# Fisierul_cu_schematicul.net
KiCad netlist of a schematic drawn in EAGLE
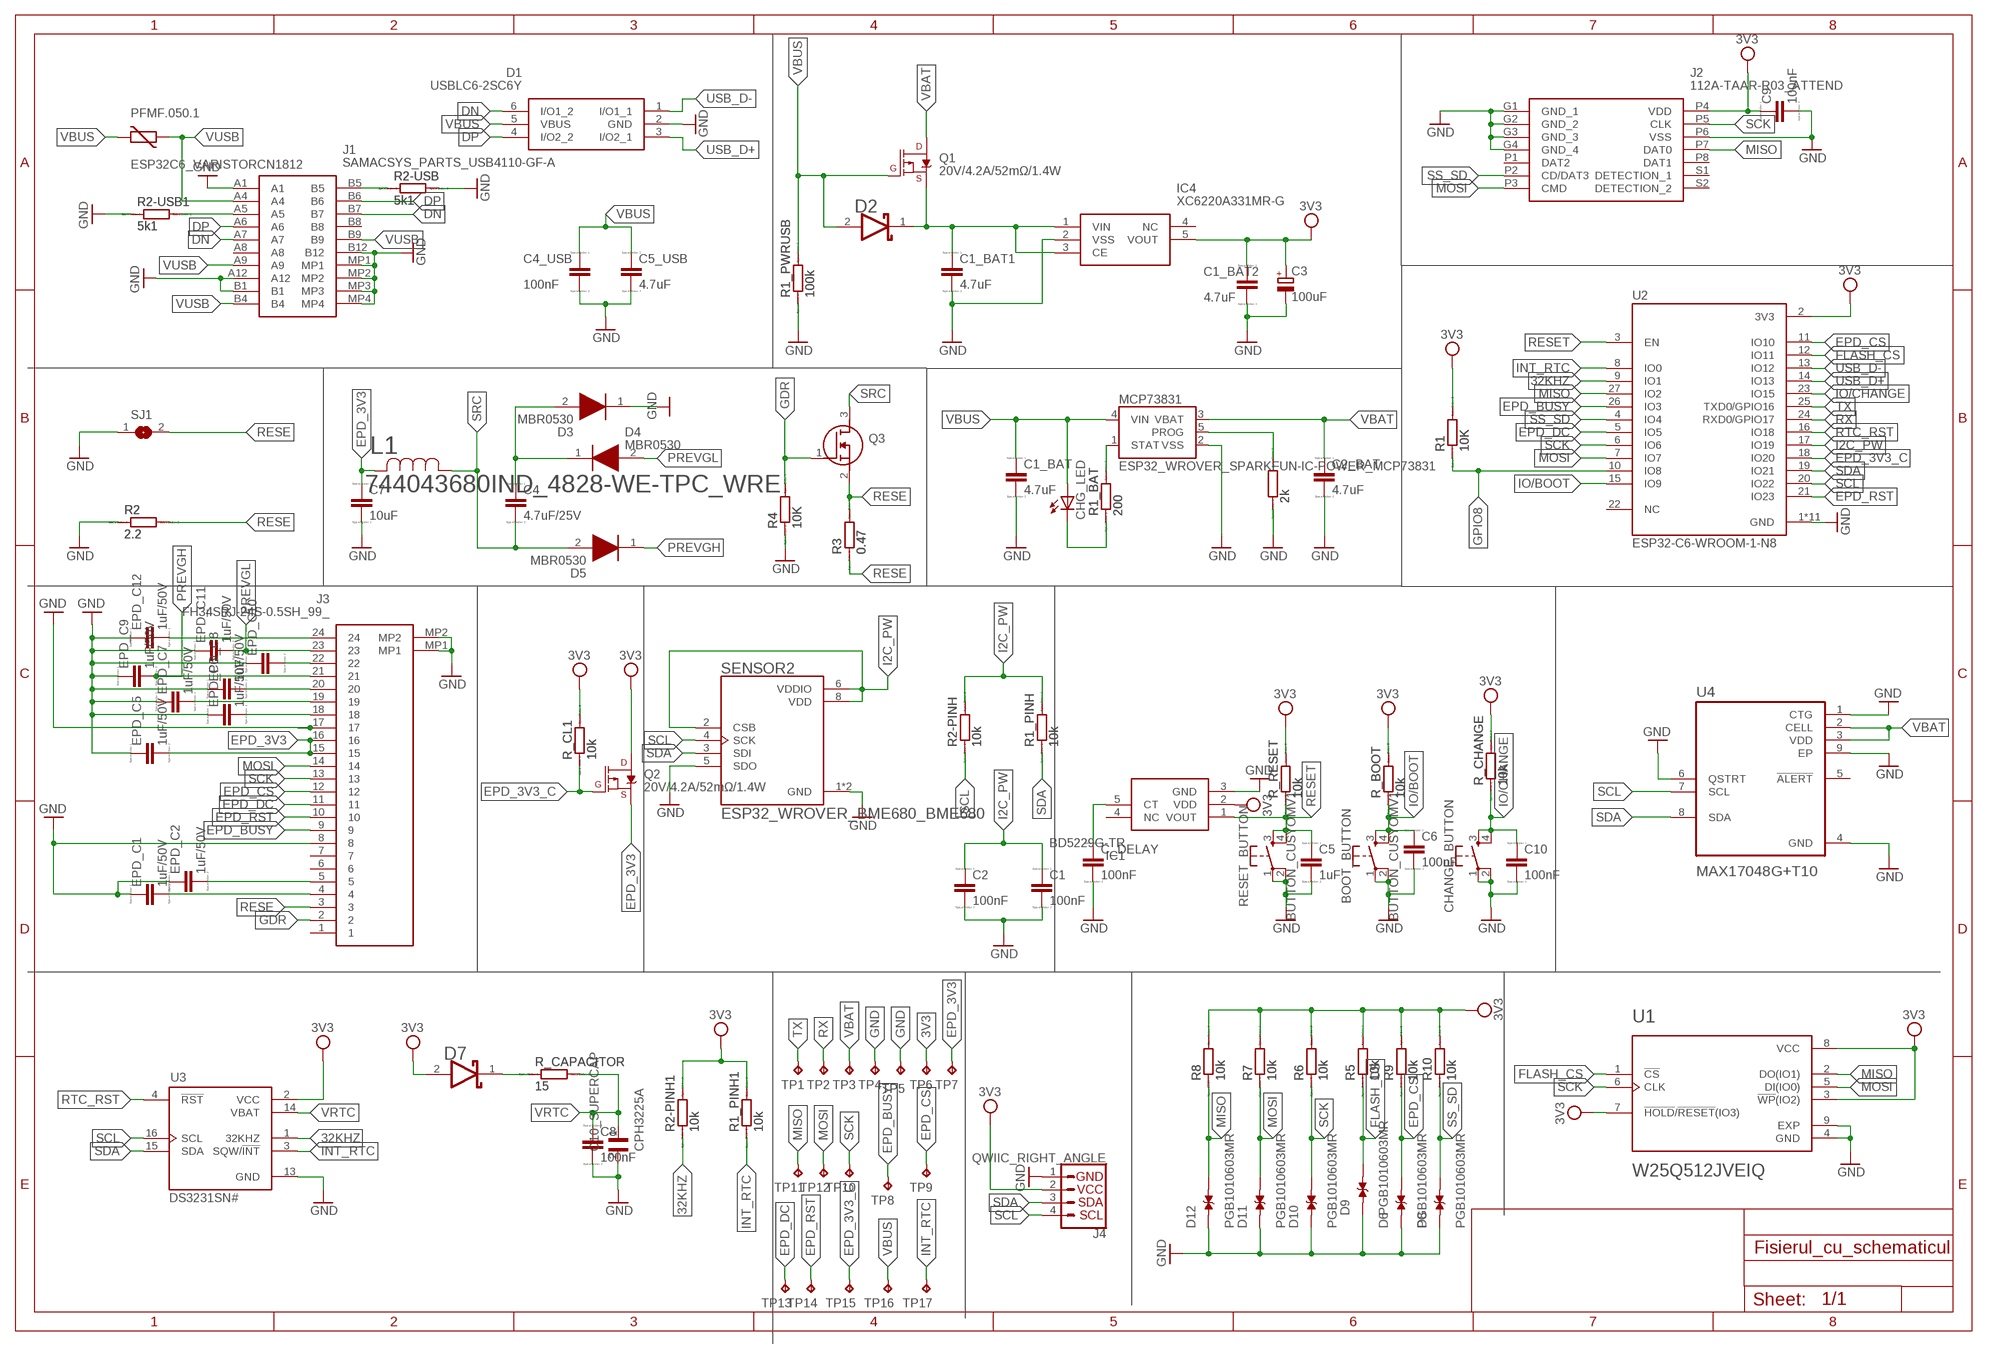
[diagram p0: schematic, sheet 1]

(export (version "E")
  (design (tool "Eeschema 10.0.6"))
  (components
    (comp (ref "BOOT_BUTTON")
      (value "BUTTON_CUSYOMV1")
      (footprint "eagle-import:MYBUTTON")
      (libsource (lib "eagle-import") (part "BUTTON_CUSYOMV1"))
    )
    (comp (ref "C1")
      (value "100nF")
      (footprint "eagle-import:EAGLE-LTSPICE_C0402")
      (libsource (lib "eagle-import") (part "EAGLE-LTSPICE_CC0402"))
    )
    (comp (ref "C1_BAT")
      (value "4.7uF")
      (footprint "eagle-import:ESP32_WROVER_EAGLE-LTSPICE_C0402")
      (libsource (lib "eagle-import") (part "ESP32_WROVER_EAGLE-LTSPICE_CC0402"))
    )
    (comp (ref "C1_BAT1")
      (value "4.7uF")
      (footprint "eagle-import:EAGLE-LTSPICE_C0402")
      (libsource (lib "eagle-import") (part "EAGLE-LTSPICE_CC0402"))
    )
    (comp (ref "C1_BAT2")
      (value "4.7uF")
      (footprint "eagle-import:EAGLE-LTSPICE_C0402")
      (libsource (lib "eagle-import") (part "EAGLE-LTSPICE_CC0402"))
    )
    (comp (ref "C2")
      (value "100nF")
      (footprint "eagle-import:EAGLE-LTSPICE_C0402")
      (libsource (lib "eagle-import") (part "EAGLE-LTSPICE_CC0402"))
    )
    (comp (ref "C2_BAT")
      (value "4.7uF")
      (footprint "eagle-import:EAGLE-LTSPICE_C0402")
      (libsource (lib "eagle-import") (part "EAGLE-LTSPICE_CC0402"))
    )
    (comp (ref "C3")
      (value "100uF")
      (footprint "eagle-import:RCL_CT3528")
      (libsource (lib "eagle-import") (part "RCL_CPOL-EUCT3528"))
    )
    (comp (ref "C4")
      (value "4.7uF/25V")
      (footprint "eagle-import:EAGLE-LTSPICE_C0402")
      (libsource (lib "eagle-import") (part "EAGLE-LTSPICE_CC0402"))
    )
    (comp (ref "C4_USB")
      (value "100nF")
      (footprint "eagle-import:ESP32_WROVER_EAGLE-LTSPICE_C0402")
      (libsource (lib "eagle-import") (part "ESP32_WROVER_EAGLE-LTSPICE_CC0402"))
    )
    (comp (ref "C5")
      (value "1uF")
      (footprint "eagle-import:EAGLE-LTSPICE_C0402")
      (libsource (lib "eagle-import") (part "EAGLE-LTSPICE_CC0402"))
    )
    (comp (ref "C5_USB")
      (value "4.7uF")
      (footprint "eagle-import:ESP32_WROVER_EAGLE-LTSPICE_C0402")
      (libsource (lib "eagle-import") (part "ESP32_WROVER_EAGLE-LTSPICE_CC0402"))
    )
    (comp (ref "C6")
      (value "100nF")
      (footprint "eagle-import:EAGLE-LTSPICE_C0402")
      (libsource (lib "eagle-import") (part "EAGLE-LTSPICE_CC0402"))
    )
    (comp (ref "C7")
      (value "10uF")
      (footprint "eagle-import:EAGLE-LTSPICE_C0402")
      (libsource (lib "eagle-import") (part "EAGLE-LTSPICE_CC0402"))
    )
    (comp (ref "C8")
      (value "100nF")
      (footprint "eagle-import:EAGLE-LTSPICE_C0402")
      (libsource (lib "eagle-import") (part "EAGLE-LTSPICE_CC0402"))
    )
    (comp (ref "C9")
      (value "100nF")
      (footprint "eagle-import:ESP32_WROVER_EAGLE-LTSPICE_C0402")
      (libsource (lib "eagle-import") (part "ESP32_WROVER_EAGLE-LTSPICE_CC0402"))
    )
    (comp (ref "C10")
      (value "100nF")
      (footprint "eagle-import:EAGLE-LTSPICE_C0402")
      (libsource (lib "eagle-import") (part "EAGLE-LTSPICE_CC0402"))
    )
    (comp (ref "C10_SUPERCAP")
      (value "CPH3225A")
      (footprint "eagle-import:CAPCP3225X100N")
      (fields (field (name "MF") "Seiko Instruments"))
      (libsource (lib "eagle-import") (part "CPH3225A"))
    )
    (comp (ref "CHANGE_BUTTON")
      (value "BUTTON_CUSYOMV1")
      (footprint "eagle-import:MYBUTTON")
      (libsource (lib "eagle-import") (part "BUTTON_CUSYOMV1"))
    )
    (comp (ref "CHG_LED")
      (value "ADAFRUIT_LEDCHIP-LED0603")
      (footprint "eagle-import:ADAFRUIT_CHIP-LED0603")
      (libsource (lib "eagle-import") (part "ADAFRUIT_LEDCHIP-LED0603"))
    )
    (comp (ref "C_DELAY")
      (value "100nF")
      (footprint "eagle-import:EAGLE-LTSPICE_C0402")
      (libsource (lib "eagle-import") (part "EAGLE-LTSPICE_CC0402"))
    )
    (comp (ref "D1")
      (value "USBLC6-2SC6Y")
      (footprint "eagle-import:SOT95P280X145-6N")
      (fields (field (name "MF") "STMicroelectronics"))
      (libsource (lib "eagle-import") (part "USBLC6-2SC6Y"))
    )
    (comp (ref "D2")
      (value "ESP32_WROVER_AVX---SD0805S020S1R0_AVX_SD0805S020S1R0_0_0AVX_SD0805S020S1R0_0_0")
      (footprint "eagle-import:ESP32_WROVER_AVX---SD0805S020S1R0_AVX_SD0805S020S1R0_0")
      (fields
        (field (name "DIGIKEY_PART_NUMBER") "478-7800-1-ND")
        (field (name "MF") "AVX")
        (field (name "MOUSER_PART_NUMBER") "581-SD0805S020S1R0")
      )
      (libsource (lib "eagle-import") (part "ESP32_WROVER_AVX---SD0805S020S1R0_AVX_SD0805S020S1R0_0_0AVX_SD0805S020S1R0_0_0"))
    )
    (comp (ref "D3")
      (value "MBR0530")
      (footprint "eagle-import:SOD3716X135N")
      (fields (field (name "MF") "ON Semiconductor"))
      (libsource (lib "eagle-import") (part "MBR0530"))
    )
    (comp (ref "D4")
      (value "MBR0530")
      (footprint "eagle-import:SOD3716X135N")
      (fields (field (name "MF") "ON Semiconductor"))
      (libsource (lib "eagle-import") (part "MBR0530"))
    )
    (comp (ref "D5")
      (value "MBR0530")
      (footprint "eagle-import:SOD3716X135N")
      (fields (field (name "MF") "ON Semiconductor"))
      (libsource (lib "eagle-import") (part "MBR0530"))
    )
    (comp (ref "D6")
      (value "PGB1010603MR")
      (footprint "eagle-import:DIOC1608X36N")
      (fields (field (name "MF") "Littelfuse Inc."))
      (libsource (lib "eagle-import") (part "PGB1010603MR"))
    )
    (comp (ref "D7")
      (value "ESP32_WROVER_AVX---SD0805S020S1R0_AVX_SD0805S020S1R0_0_0AVX_SD0805S020S1R0_0_0")
      (footprint "eagle-import:ESP32_WROVER_AVX---SD0805S020S1R0_AVX_SD0805S020S1R0_0")
      (fields
        (field (name "DIGIKEY_PART_NUMBER") "478-7800-1-ND")
        (field (name "MF") "AVX")
        (field (name "MOUSER_PART_NUMBER") "581-SD0805S020S1R0")
      )
      (libsource (lib "eagle-import") (part "ESP32_WROVER_AVX---SD0805S020S1R0_AVX_SD0805S020S1R0_0_0AVX_SD0805S020S1R0_0_0"))
    )
    (comp (ref "D8")
      (value "PGB1010603MR")
      (footprint "eagle-import:DIOC1608X36N")
      (fields (field (name "MF") "Littelfuse Inc."))
      (libsource (lib "eagle-import") (part "PGB1010603MR"))
    )
    (comp (ref "D9")
      (value "PGB1010603MR")
      (footprint "eagle-import:DIOC1608X36N")
      (fields (field (name "MF") "Littelfuse Inc."))
      (libsource (lib "eagle-import") (part "PGB1010603MR"))
    )
    (comp (ref "D10")
      (value "PGB1010603MR")
      (footprint "eagle-import:DIOC1608X36N")
      (fields (field (name "MF") "Littelfuse Inc."))
      (libsource (lib "eagle-import") (part "PGB1010603MR"))
    )
    (comp (ref "D11")
      (value "PGB1010603MR")
      (footprint "eagle-import:DIOC1608X36N")
      (fields (field (name "MF") "Littelfuse Inc."))
      (libsource (lib "eagle-import") (part "PGB1010603MR"))
    )
    (comp (ref "D12")
      (value "PGB1010603MR")
      (footprint "eagle-import:DIOC1608X36N")
      (fields (field (name "MF") "Littelfuse Inc."))
      (libsource (lib "eagle-import") (part "PGB1010603MR"))
    )
    (comp (ref "EPD_C1")
      (value "1uF/50V")
      (footprint "eagle-import:EAGLE-LTSPICE_C0402")
      (libsource (lib "eagle-import") (part "EAGLE-LTSPICE_CC0402"))
    )
    (comp (ref "EPD_C2")
      (value "1uF/50V")
      (footprint "eagle-import:EAGLE-LTSPICE_C0402")
      (libsource (lib "eagle-import") (part "EAGLE-LTSPICE_CC0402"))
    )
    (comp (ref "EPD_C5")
      (value "1uF/50V")
      (footprint "eagle-import:EAGLE-LTSPICE_C0402")
      (libsource (lib "eagle-import") (part "EAGLE-LTSPICE_CC0402"))
    )
    (comp (ref "EPD_C6")
      (value "1uF/50V")
      (footprint "eagle-import:EAGLE-LTSPICE_C0402")
      (libsource (lib "eagle-import") (part "EAGLE-LTSPICE_CC0402"))
    )
    (comp (ref "EPD_C7")
      (value "1uF/50V")
      (footprint "eagle-import:EAGLE-LTSPICE_C0402")
      (libsource (lib "eagle-import") (part "EAGLE-LTSPICE_CC0402"))
    )
    (comp (ref "EPD_C8")
      (value "1uF/50V")
      (footprint "eagle-import:EAGLE-LTSPICE_C0402")
      (libsource (lib "eagle-import") (part "EAGLE-LTSPICE_CC0402"))
    )
    (comp (ref "EPD_C9")
      (value "1uF/50V")
      (footprint "eagle-import:EAGLE-LTSPICE_C0402")
      (libsource (lib "eagle-import") (part "EAGLE-LTSPICE_CC0402"))
    )
    (comp (ref "EPD_C10")
      (value "EAGLE-LTSPICE_CC0402")
      (footprint "eagle-import:EAGLE-LTSPICE_C0402")
      (libsource (lib "eagle-import") (part "EAGLE-LTSPICE_CC0402"))
    )
    (comp (ref "EPD_C11")
      (value "1uF/50V")
      (footprint "eagle-import:EAGLE-LTSPICE_C0402")
      (libsource (lib "eagle-import") (part "EAGLE-LTSPICE_CC0402"))
    )
    (comp (ref "EPD_C12")
      (value "1uF/50V")
      (footprint "eagle-import:EAGLE-LTSPICE_C0402")
      (libsource (lib "eagle-import") (part "EAGLE-LTSPICE_CC0402"))
    )
    (comp (ref "IC1")
      (value "BD5229G-TR")
      (footprint "eagle-import:SOT95P280X125-5N")
      (fields (field (name "MOUSER_PART_NUMBER") "755-BD5229G-TR"))
      (libsource (lib "eagle-import") (part "BD5229G-TR"))
    )
    (comp (ref "IC4")
      (value "XC6220A331MR-G")
      (footprint "eagle-import:SOT95P280X120-5N")
      (fields (field (name "MOUSER_PART_NUMBER") "865-XC6220A331MR-G"))
      (libsource (lib "eagle-import") (part "XC6220A331MR-G"))
    )
    (comp (ref "J1")
      (value "SAMACSYS_PARTS_USB4110-GF-A")
      (footprint "eagle-import:SAMACSYS_PARTS_USB4110GFA")
      (fields
        (field (name "MANUFACTURER_PART_NUMBER") "USB4110-GF-A")
        (field (name "MOUSER_PART_NUMBER") "640-USB4110-GF-A")
      )
      (libsource (lib "eagle-import") (part "SAMACSYS_PARTS_USB4110-GF-A"))
    )
    (comp (ref "J2")
      (value "112A-TAAR-R03_ATTEND")
      (footprint "eagle-import:112ATAARR03ATTEND")
      (fields (field (name "MANUFACTURER_PART_NUMBER") "112A-TAAR-R03 ATTEND"))
      (libsource (lib "eagle-import") (part "112A-TAAR-R03_ATTEND"))
    )
    (comp (ref "J3")
      (value "FH34SRJ-24S-0.5SH_99_")
      (footprint "eagle-import:FH34SRJ24S05SH99")
      (fields
        (field (name "MANUFACTURER_PART_NUMBER") "FH34SRJ-24S-0.5SH(99)")
        (field (name "MOUSER_PART_NUMBER") "798-FH34SRJ24S05SH99")
      )
      (libsource (lib "eagle-import") (part "FH34SRJ-24S-0.5SH_99_"))
    )
    (comp (ref "J4")
      (value "QWIIC_RIGHT_ANGLE")
      (footprint "eagle-import:JST04_1MM_RA")
      (libsource (lib "eagle-import") (part "QWIIC_CONNECTORJS-1MM"))
    )
    (comp (ref "L1")
      (value "744043680IND_4828-WE-TPC_WRE")
      (footprint "eagle-import:IND_4828-WE-TPC_WRE")
      (fields
        (field (name "MANUFACTURER_PART_NUMBER") "744043680")
        (field (name "COPYRIGHT") "Copyright (C) 2024 Ultra Librarian. All rights reserved.")
      )
      (libsource (lib "eagle-import") (part "744043680IND_4828-WE-TPC_WRE"))
    )
    (comp (ref "MCP73831")
      (value "ESP32_WROVER_SPARKFUN-IC-POWER_MCP73831")
      (footprint "eagle-import:ESP32_WROVER_SPARKFUN-IC-POWER_SOT23-5")
      (libsource (lib "eagle-import") (part "ESP32_WROVER_SPARKFUN-IC-POWER_MCP73831"))
    )
    (comp (ref "PFMF.050.1")
      (value "ESP32C6_VARISTORCN1812")
      (footprint "eagle-import:ESP32C6_VARISTOR_CT_CN1812")
      (libsource (lib "eagle-import") (part "ESP32C6_VARISTORCN1812"))
    )
    (comp (ref "Q1")
      (value "20V/4.2A/52mΩ/1.4W")
      (footprint "eagle-import:ESP32_WROVER_SPARKFUN-DISCRETESEMI_SOT23-3")
      (libsource (lib "eagle-import") (part "ESP32_WROVER_SPARKFUN-DISCRETESEMI_MOSFET_PCH-DMG2305UX-7"))
    )
    (comp (ref "Q2")
      (value "20V/4.2A/52mΩ/1.4W")
      (footprint "eagle-import:ESP32_WROVER_SPARKFUN-DISCRETESEMI_SOT23-3")
      (libsource (lib "eagle-import") (part "ESP32_WROVER_SPARKFUN-DISCRETESEMI_MOSFET_PCH-DMG2305UX-7"))
    )
    (comp (ref "Q3")
      (value "SI1308EDL-T1-GE3")
      (footprint "eagle-import:SOT65P210X110-3N")
      (fields (field (name "MF") "Vishay Siliconix"))
      (libsource (lib "eagle-import") (part "SI1308EDL-T1-GE3"))
    )
    (comp (ref "R1")
      (value "10K")
      (footprint "eagle-import:ESP32_WROVER_EAGLE-LTSPICE_R0402")
      (libsource (lib "eagle-import") (part "ESP32_WROVER_EAGLE-LTSPICE_RR0402"))
    )
    (comp (ref "R1_BAT")
      (value "200")
      (footprint "eagle-import:ESP32_WROVER_EAGLE-LTSPICE_R0402")
      (libsource (lib "eagle-import") (part "ESP32_WROVER_EAGLE-LTSPICE_RR0402"))
    )
    (comp (ref "R1_PINH")
      (value "10k")
      (footprint "eagle-import:ESP32_WROVER_EAGLE-LTSPICE_R0402")
      (libsource (lib "eagle-import") (part "ESP32_WROVER_EAGLE-LTSPICE_RR0402"))
    )
    (comp (ref "R1_PINH1")
      (value "10k")
      (footprint "eagle-import:ESP32_WROVER_EAGLE-LTSPICE_R0402")
      (libsource (lib "eagle-import") (part "ESP32_WROVER_EAGLE-LTSPICE_RR0402"))
    )
    (comp (ref "R1_PWRUSB")
      (value "100k")
      (footprint "eagle-import:ESP32_WROVER_EAGLE-LTSPICE_R0402")
      (libsource (lib "eagle-import") (part "ESP32_WROVER_EAGLE-LTSPICE_RR0402"))
    )
    (comp (ref "R2")
      (value "2.2")
      (footprint "eagle-import:ESP32_WROVER_EAGLE-LTSPICE_R0402")
      (libsource (lib "eagle-import") (part "ESP32_WROVER_EAGLE-LTSPICE_RR0402"))
    )
    (comp (ref "R2-PINH")
      (value "10k")
      (footprint "eagle-import:ESP32_WROVER_EAGLE-LTSPICE_R0402")
      (libsource (lib "eagle-import") (part "ESP32_WROVER_EAGLE-LTSPICE_RR0402"))
    )
    (comp (ref "R2-PINH1")
      (value "10k")
      (footprint "eagle-import:ESP32_WROVER_EAGLE-LTSPICE_R0402")
      (libsource (lib "eagle-import") (part "ESP32_WROVER_EAGLE-LTSPICE_RR0402"))
    )
    (comp (ref "R2-USB")
      (value "5k1")
      (footprint "eagle-import:ESP32_WROVER_EAGLE-LTSPICE_R0402")
      (libsource (lib "eagle-import") (part "ESP32_WROVER_EAGLE-LTSPICE_RR0402"))
    )
    (comp (ref "R2-USB1")
      (value "5k1")
      (footprint "eagle-import:ESP32_WROVER_EAGLE-LTSPICE_R0402")
      (libsource (lib "eagle-import") (part "ESP32_WROVER_EAGLE-LTSPICE_RR0402"))
    )
    (comp (ref "R2_BAT")
      (value "2k")
      (footprint "eagle-import:ESP32_WROVER_EAGLE-LTSPICE_R0402")
      (libsource (lib "eagle-import") (part "ESP32_WROVER_EAGLE-LTSPICE_RR0402"))
    )
    (comp (ref "R3")
      (value "0.47")
      (footprint "eagle-import:ESP32_WROVER_EAGLE-LTSPICE_R0402")
      (libsource (lib "eagle-import") (part "ESP32_WROVER_EAGLE-LTSPICE_RR0402"))
    )
    (comp (ref "R4")
      (value "10K")
      (footprint "eagle-import:ESP32_WROVER_EAGLE-LTSPICE_R0402")
      (libsource (lib "eagle-import") (part "ESP32_WROVER_EAGLE-LTSPICE_RR0402"))
    )
    (comp (ref "R5")
      (value "10k")
      (footprint "eagle-import:ESP32_WROVER_EAGLE-LTSPICE_R0402")
      (libsource (lib "eagle-import") (part "ESP32_WROVER_EAGLE-LTSPICE_RR0402"))
    )
    (comp (ref "R6")
      (value "10k")
      (footprint "eagle-import:ESP32_WROVER_EAGLE-LTSPICE_R0402")
      (libsource (lib "eagle-import") (part "ESP32_WROVER_EAGLE-LTSPICE_RR0402"))
    )
    (comp (ref "R7")
      (value "10k")
      (footprint "eagle-import:ESP32_WROVER_EAGLE-LTSPICE_R0402")
      (libsource (lib "eagle-import") (part "ESP32_WROVER_EAGLE-LTSPICE_RR0402"))
    )
    (comp (ref "R8")
      (value "10k")
      (footprint "eagle-import:ESP32_WROVER_EAGLE-LTSPICE_R0402")
      (libsource (lib "eagle-import") (part "ESP32_WROVER_EAGLE-LTSPICE_RR0402"))
    )
    (comp (ref "R9")
      (value "10k")
      (footprint "eagle-import:ESP32_WROVER_EAGLE-LTSPICE_R0402")
      (libsource (lib "eagle-import") (part "ESP32_WROVER_EAGLE-LTSPICE_RR0402"))
    )
    (comp (ref "R10")
      (value "10k")
      (footprint "eagle-import:ESP32_WROVER_EAGLE-LTSPICE_R0402")
      (libsource (lib "eagle-import") (part "ESP32_WROVER_EAGLE-LTSPICE_RR0402"))
    )
    (comp (ref "RESET_BUTTON")
      (value "BUTTON_CUSYOMV1")
      (footprint "eagle-import:MYBUTTON")
      (libsource (lib "eagle-import") (part "BUTTON_CUSYOMV1"))
    )
    (comp (ref "R_BOOT")
      (value "10k")
      (footprint "eagle-import:ESP32_WROVER_EAGLE-LTSPICE_R0402")
      (libsource (lib "eagle-import") (part "ESP32_WROVER_EAGLE-LTSPICE_RR0402"))
    )
    (comp (ref "R_CAPACITOR")
      (value "15")
      (footprint "eagle-import:ESP32_WROVER_EAGLE-LTSPICE_R0402")
      (libsource (lib "eagle-import") (part "ESP32_WROVER_EAGLE-LTSPICE_RR0402"))
    )
    (comp (ref "R_CHANGE")
      (value "10k")
      (footprint "eagle-import:ESP32_WROVER_EAGLE-LTSPICE_R0402")
      (libsource (lib "eagle-import") (part "ESP32_WROVER_EAGLE-LTSPICE_RR0402"))
    )
    (comp (ref "R_CL1")
      (value "10k")
      (footprint "eagle-import:ESP32_WROVER_EAGLE-LTSPICE_R0402")
      (libsource (lib "eagle-import") (part "ESP32_WROVER_EAGLE-LTSPICE_RR0402"))
    )
    (comp (ref "R_RESET")
      (value "10k")
      (footprint "eagle-import:ESP32_WROVER_EAGLE-LTSPICE_R0402")
      (libsource (lib "eagle-import") (part "ESP32_WROVER_EAGLE-LTSPICE_RR0402"))
    )
    (comp (ref "SENSOR2")
      (value "ESP32_WROVER_BME680_BME680")
      (footprint "eagle-import:ESP32_WROVER_BME680_PSON80P300X300X100-8N")
      (fields (field (name "MF") "Bosch Sensortec") (field (name "MP") "BME680"))
      (libsource (lib "eagle-import") (part "ESP32_WROVER_BME680_BME680"))
    )
    (comp (ref "SJ1") (value "SJ") (footprint "eagle-import:SJ") (libsource (lib "eagle-import") (part "SJ")))
    (comp (ref "TP1")
      (value "TPTP20R")
      (footprint "eagle-import:TP20R")
      (libsource (lib "eagle-import") (part "TPTP20R"))
    )
    (comp (ref "TP2")
      (value "TPTP20R")
      (footprint "eagle-import:TP20R")
      (libsource (lib "eagle-import") (part "TPTP20R"))
    )
    (comp (ref "TP3")
      (value "TPTP20R")
      (footprint "eagle-import:TP20R")
      (libsource (lib "eagle-import") (part "TPTP20R"))
    )
    (comp (ref "TP4")
      (value "TPTP20R")
      (footprint "eagle-import:TP20R")
      (libsource (lib "eagle-import") (part "TPTP20R"))
    )
    (comp (ref "TP5")
      (value "TPTP20R")
      (footprint "eagle-import:TP20R")
      (libsource (lib "eagle-import") (part "TPTP20R"))
    )
    (comp (ref "TP6")
      (value "TPTP20R")
      (footprint "eagle-import:TP20R")
      (libsource (lib "eagle-import") (part "TPTP20R"))
    )
    (comp (ref "TP7")
      (value "TPTP20R")
      (footprint "eagle-import:TP20R")
      (libsource (lib "eagle-import") (part "TPTP20R"))
    )
    (comp (ref "TP8")
      (value "TPTP20R")
      (footprint "eagle-import:TP20R")
      (libsource (lib "eagle-import") (part "TPTP20R"))
    )
    (comp (ref "TP9")
      (value "TPTP20R")
      (footprint "eagle-import:TP20R")
      (libsource (lib "eagle-import") (part "TPTP20R"))
    )
    (comp (ref "TP10")
      (value "TPTP20R")
      (footprint "eagle-import:TP20R")
      (libsource (lib "eagle-import") (part "TPTP20R"))
    )
    (comp (ref "TP11")
      (value "TPTP20R")
      (footprint "eagle-import:TP20R")
      (libsource (lib "eagle-import") (part "TPTP20R"))
    )
    (comp (ref "TP12")
      (value "TPTP20R")
      (footprint "eagle-import:TP20R")
      (libsource (lib "eagle-import") (part "TPTP20R"))
    )
    (comp (ref "TP13")
      (value "TPTP20R")
      (footprint "eagle-import:TP20R")
      (libsource (lib "eagle-import") (part "TPTP20R"))
    )
    (comp (ref "TP14")
      (value "TPTP20R")
      (footprint "eagle-import:TP20R")
      (libsource (lib "eagle-import") (part "TPTP20R"))
    )
    (comp (ref "TP15")
      (value "TPTP20R")
      (footprint "eagle-import:TP20R")
      (libsource (lib "eagle-import") (part "TPTP20R"))
    )
    (comp (ref "TP16")
      (value "TPTP20R")
      (footprint "eagle-import:TP20R")
      (libsource (lib "eagle-import") (part "TPTP20R"))
    )
    (comp (ref "TP17")
      (value "TPTP20R")
      (footprint "eagle-import:TP20R")
      (libsource (lib "eagle-import") (part "TPTP20R"))
    )
    (comp (ref "U1")
      (value "W25Q512JVEIQ")
      (footprint "eagle-import:SON127P600X800X80-9N")
      (fields (field (name "MF") "Winbond Electronics"))
      (libsource (lib "eagle-import") (part "W25Q512JVEIQ"))
    )
    (comp (ref "U2")
      (value "ESP32-C6-WROOM-1-N8")
      (footprint "eagle-import:XCVR_ESP32-C6-WROOM-1-N8")
      (fields (field (name "MF") "Espressif Systems"))
      (libsource (lib "eagle-import") (part "ESP32-C6-WROOM-1-N8"))
    )
    (comp (ref "U3")
      (value "DS3231SN#")
      (footprint "eagle-import:SOIC127P1032X265-16N")
      (fields (field (name "MF") "Analog Devices"))
      (libsource (lib "eagle-import") (part "DS3231SN#"))
    )
    (comp (ref "U4")
      (value "MAX17048G+T10")
      (footprint "eagle-import:SON50P200X200X80-9N")
      (fields (field (name "MF") "Analog Devices"))
      (libsource (lib "eagle-import") (part "MAX17048G+T10"))
    )
  )
  (nets
    (net (code "1") (name "3V3") (class "Default")
      (node (ref "C1_BAT2") (pin "1") (pinfunction "1_1") (pintype "passive"))
      (node (ref "C3") (pin "+") (pinfunction "+_+") (pintype "passive"))
      (node (ref "C9") (pin "1") (pinfunction "1_1") (pintype "passive"))
      (node (ref "D7") (pin "2") (pinfunction "ANODE_2") (pintype "bidirectional"))
      (node (ref "IC1") (pin "2") (pinfunction "VDD_2") (pintype "bidirectional"))
      (node (ref "IC4") (pin "5") (pinfunction "VOUT_5") (pintype "bidirectional"))
      (node (ref "J2") (pin "P4") (pinfunction "VDD_P4") (pintype "bidirectional"))
      (node (ref "J4") (pin "2") (pinfunction "2_2") (pintype "power_in"))
      (node (ref "Q2") (pin "3") (pinfunction "D_3") (pintype "bidirectional"))
      (node (ref "R1") (pin "2") (pinfunction "2_2") (pintype "passive"))
      (node (ref "R10") (pin "2") (pinfunction "2_2") (pintype "passive"))
      (node (ref "R1_PINH1") (pin "2") (pinfunction "2_2") (pintype "passive"))
      (node (ref "R2-PINH1") (pin "2") (pinfunction "2_2") (pintype "passive"))
      (node (ref "R5") (pin "2") (pinfunction "2_2") (pintype "passive"))
      (node (ref "R6") (pin "2") (pinfunction "2_2") (pintype "passive"))
      (node (ref "R7") (pin "2") (pinfunction "2_2") (pintype "passive"))
      (node (ref "R8") (pin "2") (pinfunction "2_2") (pintype "passive"))
      (node (ref "R9") (pin "2") (pinfunction "2_2") (pintype "passive"))
      (node (ref "R_BOOT") (pin "2") (pinfunction "2_2") (pintype "passive"))
      (node (ref "R_CHANGE") (pin "2") (pinfunction "2_2") (pintype "passive"))
      (node (ref "R_CL1") (pin "2") (pinfunction "2_2") (pintype "passive"))
      (node (ref "R_RESET") (pin "2") (pinfunction "2_2") (pintype "passive"))
      (node (ref "TP6") (pin "TP") (pinfunction "TP_TP") (pintype "input"))
      (node (ref "U1") (pin "3") (pinfunction "~{WP}(IO2)_3") (pintype "bidirectional"))
      (node (ref "U1") (pin "7") (pinfunction "~{HOLD}/~{RESET}(IO3)_7") (pintype "bidirectional"))
      (node (ref "U1") (pin "8") (pinfunction "VCC_8") (pintype "power_in"))
      (node (ref "U2") (pin "2") (pinfunction "3V3_2") (pintype "power_in"))
      (node (ref "U3") (pin "2") (pinfunction "VCC_2") (pintype "power_in"))
    )
    (net (code "2") (name "32KHZ") (class "Default")
      (node (ref "R2-PINH1") (pin "1") (pinfunction "1_1") (pintype "passive"))
      (node (ref "U2") (pin "9") (pinfunction "IO1_9") (pintype "bidirectional"))
      (node (ref "U3") (pin "1") (pinfunction "32KHZ_1") (pintype "output"))
    )
    (net (code "3") (name "DN") (class "Default")
      (node (ref "D1") (pin "6") (pinfunction "I/O1_2_6") (pintype "bidirectional"))
      (node (ref "J1") (pin "A7") (pinfunction "A7_A7") (pintype "bidirectional"))
      (node (ref "J1") (pin "B7") (pinfunction "B7_B7") (pintype "bidirectional"))
    )
    (net (code "4") (name "DP") (class "Default")
      (node (ref "D1") (pin "4") (pinfunction "I/O2_2_4") (pintype "bidirectional"))
      (node (ref "J1") (pin "A6") (pinfunction "A6_A6") (pintype "bidirectional"))
      (node (ref "J1") (pin "B6") (pinfunction "B6_B6") (pintype "bidirectional"))
    )
    (net (code "5") (name "EPD_3V3") (class "Default")
      (node (ref "C7") (pin "1") (pinfunction "1_1") (pintype "passive"))
      (node (ref "EPD_C5") (pin "2") (pinfunction "2_2") (pintype "passive"))
      (node (ref "J3") (pin "15") (pinfunction "15_15") (pintype "bidirectional"))
      (node (ref "J3") (pin "16") (pinfunction "16_16") (pintype "bidirectional"))
      (node (ref "L1") (pin "2") (pinfunction "2_2") (pintype "passive"))
      (node (ref "Q2") (pin "2") (pinfunction "S_2") (pintype "bidirectional"))
      (node (ref "TP7") (pin "TP") (pinfunction "TP_TP") (pintype "input"))
    )
    (net (code "6") (name "EPD_3V3_C") (class "Default")
      (node (ref "Q2") (pin "1") (pinfunction "G_1") (pintype "bidirectional"))
      (node (ref "R_CL1") (pin "1") (pinfunction "1_1") (pintype "passive"))
      (node (ref "TP15") (pin "TP") (pinfunction "TP_TP") (pintype "input"))
      (node (ref "U2") (pin "18") (pinfunction "IO20_18") (pintype "bidirectional"))
    )
    (net (code "7") (name "EPD_BUSY") (class "Default")
      (node (ref "J3") (pin "9") (pinfunction "9_9") (pintype "bidirectional"))
      (node (ref "TP8") (pin "TP") (pinfunction "TP_TP") (pintype "input"))
      (node (ref "U2") (pin "26") (pinfunction "IO3_26") (pintype "bidirectional"))
    )
    (net (code "8") (name "EPD_CS") (class "Default")
      (node (ref "D6") (pin "2") (pinfunction "2_2") (pintype "passive"))
      (node (ref "J3") (pin "12") (pinfunction "12_12") (pintype "bidirectional"))
      (node (ref "R9") (pin "1") (pinfunction "1_1") (pintype "passive"))
      (node (ref "TP9") (pin "TP") (pinfunction "TP_TP") (pintype "input"))
      (node (ref "U2") (pin "11") (pinfunction "IO10_11") (pintype "bidirectional"))
    )
    (net (code "9") (name "EPD_DC") (class "Default")
      (node (ref "J3") (pin "11") (pinfunction "11_11") (pintype "bidirectional"))
      (node (ref "TP13") (pin "TP") (pinfunction "TP_TP") (pintype "input"))
      (node (ref "U2") (pin "5") (pinfunction "IO5_5") (pintype "bidirectional"))
    )
    (net (code "10") (name "EPD_RST") (class "Default")
      (node (ref "J3") (pin "10") (pinfunction "10_10") (pintype "bidirectional"))
      (node (ref "TP14") (pin "TP") (pinfunction "TP_TP") (pintype "input"))
      (node (ref "U2") (pin "21") (pinfunction "IO23_21") (pintype "bidirectional"))
    )
    (net (code "11") (name "FLASH_CS") (class "Default")
      (node (ref "D9") (pin "2") (pinfunction "2_2") (pintype "passive"))
      (node (ref "R5") (pin "1") (pinfunction "1_1") (pintype "passive"))
      (node (ref "U1") (pin "1") (pinfunction "~{CS}_1") (pintype "input"))
      (node (ref "U2") (pin "12") (pinfunction "IO11_12") (pintype "bidirectional"))
    )
    (net (code "12") (name "GDR") (class "Default")
      (node (ref "J3") (pin "2") (pinfunction "2_2") (pintype "bidirectional"))
      (node (ref "Q3") (pin "1") (pinfunction "G_1") (pintype "bidirectional"))
      (node (ref "R4") (pin "2") (pinfunction "2_2") (pintype "passive"))
    )
    (net (code "13") (name "GND") (class "Default")
      (node (ref "BOOT_BUTTON") (pin "1") (pinfunction "1_1") (pintype "passive"))
      (node (ref "BOOT_BUTTON") (pin "2") (pinfunction "2_2") (pintype "passive"))
      (node (ref "C1") (pin "2") (pinfunction "2_2") (pintype "passive"))
      (node (ref "C10") (pin "2") (pinfunction "2_2") (pintype "passive"))
      (node (ref "C10_SUPERCAP") (pin "2") (pinfunction "2_2") (pintype "passive"))
      (node (ref "C1_BAT") (pin "2") (pinfunction "2_2") (pintype "passive"))
      (node (ref "C1_BAT1") (pin "2") (pinfunction "2_2") (pintype "passive"))
      (node (ref "C1_BAT2") (pin "2") (pinfunction "2_2") (pintype "passive"))
      (node (ref "C2") (pin "2") (pinfunction "2_2") (pintype "passive"))
      (node (ref "C2_BAT") (pin "2") (pinfunction "2_2") (pintype "passive"))
      (node (ref "C3") (pin "-") (pinfunction "-_-") (pintype "passive"))
      (node (ref "C4_USB") (pin "2") (pinfunction "2_2") (pintype "passive"))
      (node (ref "C5") (pin "2") (pinfunction "2_2") (pintype "passive"))
      (node (ref "C5_USB") (pin "2") (pinfunction "2_2") (pintype "passive"))
      (node (ref "C6") (pin "2") (pinfunction "2_2") (pintype "passive"))
      (node (ref "C7") (pin "2") (pinfunction "2_2") (pintype "passive"))
      (node (ref "C8") (pin "2") (pinfunction "2_2") (pintype "passive"))
      (node (ref "C9") (pin "2") (pinfunction "2_2") (pintype "passive"))
      (node (ref "CHANGE_BUTTON") (pin "1") (pinfunction "1_1") (pintype "passive"))
      (node (ref "CHANGE_BUTTON") (pin "2") (pinfunction "2_2") (pintype "passive"))
      (node (ref "C_DELAY") (pin "2") (pinfunction "2_2") (pintype "passive"))
      (node (ref "D1") (pin "2") (pinfunction "GND_2") (pintype "bidirectional"))
      (node (ref "D10") (pin "1") (pinfunction "1_1") (pintype "passive"))
      (node (ref "D11") (pin "1") (pinfunction "1_1") (pintype "passive"))
      (node (ref "D12") (pin "1") (pinfunction "1_1") (pintype "passive"))
      (node (ref "D3") (pin "1") (pinfunction "K_1") (pintype "bidirectional"))
      (node (ref "D6") (pin "1") (pinfunction "1_1") (pintype "passive"))
      (node (ref "D8") (pin "1") (pinfunction "1_1") (pintype "passive"))
      (node (ref "D9") (pin "1") (pinfunction "1_1") (pintype "passive"))
      (node (ref "EPD_C1") (pin "1") (pinfunction "1_1") (pintype "passive"))
      (node (ref "EPD_C10") (pin "1") (pinfunction "1_1") (pintype "passive"))
      (node (ref "EPD_C11") (pin "1") (pinfunction "1_1") (pintype "passive"))
      (node (ref "EPD_C12") (pin "1") (pinfunction "1_1") (pintype "passive"))
      (node (ref "EPD_C2") (pin "1") (pinfunction "1_1") (pintype "passive"))
      (node (ref "EPD_C5") (pin "1") (pinfunction "1_1") (pintype "passive"))
      (node (ref "EPD_C6") (pin "1") (pinfunction "1_1") (pintype "passive"))
      (node (ref "EPD_C7") (pin "1") (pinfunction "1_1") (pintype "passive"))
      (node (ref "EPD_C8") (pin "1") (pinfunction "1_1") (pintype "passive"))
      (node (ref "EPD_C9") (pin "1") (pinfunction "1_1") (pintype "passive"))
      (node (ref "IC1") (pin "3") (pinfunction "GND_3") (pintype "bidirectional"))
      (node (ref "IC4") (pin "2") (pinfunction "VSS_2") (pintype "bidirectional"))
      (node (ref "J1") (pin "A1") (pinfunction "A1_A1") (pintype "bidirectional"))
      (node (ref "J1") (pin "A12") (pinfunction "A12_A12") (pintype "bidirectional"))
      (node (ref "J1") (pin "B1") (pinfunction "B1_B1") (pintype "bidirectional"))
      (node (ref "J1") (pin "B12") (pinfunction "B12_B12") (pintype "bidirectional"))
      (node (ref "J1") (pin "MP1") (pinfunction "MP1_MP1") (pintype "bidirectional"))
      (node (ref "J1") (pin "MP2") (pinfunction "MP2_MP2") (pintype "bidirectional"))
      (node (ref "J1") (pin "MP3") (pinfunction "MP3_MP3") (pintype "bidirectional"))
      (node (ref "J1") (pin "MP4") (pinfunction "MP4_MP4") (pintype "bidirectional"))
      (node (ref "J2") (pin "G1") (pinfunction "GND_1_G1") (pintype "bidirectional"))
      (node (ref "J2") (pin "G2") (pinfunction "GND_2_G2") (pintype "bidirectional"))
      (node (ref "J2") (pin "G3") (pinfunction "GND_3_G3") (pintype "bidirectional"))
      (node (ref "J2") (pin "G4") (pinfunction "GND_4_G4") (pintype "bidirectional"))
      (node (ref "J2") (pin "P6") (pinfunction "VSS_P6") (pintype "bidirectional"))
      (node (ref "J3") (pin "17") (pinfunction "17_17") (pintype "bidirectional"))
      (node (ref "J3") (pin "8") (pinfunction "8_8") (pintype "bidirectional"))
      (node (ref "J3") (pin "MP1") (pinfunction "MP1_MP1") (pintype "bidirectional"))
      (node (ref "J3") (pin "MP2") (pinfunction "MP2_MP2") (pintype "bidirectional"))
      (node (ref "J4") (pin "1") (pinfunction "1_1") (pintype "power_in"))
      (node (ref "MCP73831") (pin "2") (pinfunction "VSS_2") (pintype "power_in"))
      (node (ref "R1_PWRUSB") (pin "1") (pinfunction "1_1") (pintype "passive"))
      (node (ref "R2") (pin "1") (pinfunction "1_1") (pintype "passive"))
      (node (ref "R2-USB") (pin "2") (pinfunction "2_2") (pintype "passive"))
      (node (ref "R2-USB1") (pin "1") (pinfunction "1_1") (pintype "passive"))
      (node (ref "R2_BAT") (pin "1") (pinfunction "1_1") (pintype "passive"))
      (node (ref "R4") (pin "1") (pinfunction "1_1") (pintype "passive"))
      (node (ref "RESET_BUTTON") (pin "1") (pinfunction "1_1") (pintype "passive"))
      (node (ref "RESET_BUTTON") (pin "2") (pinfunction "2_2") (pintype "passive"))
      (node (ref "SENSOR2") (pin "1") (pinfunction "GND_1") (pintype "power_in"))
      (node (ref "SENSOR2") (pin "5") (pinfunction "SDO_5") (pintype "bidirectional"))
      (node (ref "SENSOR2") (pin "7") (pinfunction "GND_7") (pintype "power_in"))
      (node (ref "SJ1") (pin "1") (pinfunction "1_1") (pintype "passive"))
      (node (ref "TP4") (pin "TP") (pinfunction "TP_TP") (pintype "input"))
      (node (ref "TP5") (pin "TP") (pinfunction "TP_TP") (pintype "input"))
      (node (ref "U1") (pin "4") (pinfunction "GND_4") (pintype "power_in"))
      (node (ref "U1") (pin "9") (pinfunction "EXP_9") (pintype "passive"))
      (node (ref "U2") (pin "1") (pinfunction "GND_1") (pintype "power_in"))
      (node (ref "U2") (pin "28") (pinfunction "GND_28") (pintype "power_in"))
      (node (ref "U2") (pin "29_1") (pinfunction "GND_29_1") (pintype "power_in"))
      (node (ref "U2") (pin "29_2") (pinfunction "GND_29_2") (pintype "power_in"))
      (node (ref "U2") (pin "29_3") (pinfunction "GND_29_3") (pintype "power_in"))
      (node (ref "U2") (pin "29_4") (pinfunction "GND_29_4") (pintype "power_in"))
      (node (ref "U2") (pin "29_5") (pinfunction "GND_29_5") (pintype "power_in"))
      (node (ref "U2") (pin "29_6") (pinfunction "GND_29_6") (pintype "power_in"))
      (node (ref "U2") (pin "29_7") (pinfunction "GND_29_7") (pintype "power_in"))
      (node (ref "U2") (pin "29_8") (pinfunction "GND_29_8") (pintype "power_in"))
      (node (ref "U2") (pin "29_9") (pinfunction "GND_29_9") (pintype "power_in"))
      (node (ref "U3") (pin "13") (pinfunction "GND_13") (pintype "power_in"))
      (node (ref "U4") (pin "1") (pinfunction "CTG_1") (pintype "power_in"))
      (node (ref "U4") (pin "4") (pinfunction "GND_4") (pintype "power_in"))
      (node (ref "U4") (pin "6") (pinfunction "QSTRT_6") (pintype "input"))
      (node (ref "U4") (pin "9") (pinfunction "EP_9") (pintype "power_in"))
    )
    (net (code "14") (name "GPIO8") (class "Default")
      (node (ref "R1") (pin "1") (pinfunction "1_1") (pintype "passive"))
      (node (ref "U2") (pin "10") (pinfunction "IO8_10") (pintype "bidirectional"))
    )
    (net (code "15") (name "I2C_PW") (class "Default")
      (node (ref "C1") (pin "1") (pinfunction "1_1") (pintype "passive"))
      (node (ref "C2") (pin "1") (pinfunction "1_1") (pintype "passive"))
      (node (ref "R1_PINH") (pin "2") (pinfunction "2_2") (pintype "passive"))
      (node (ref "R2-PINH") (pin "2") (pinfunction "2_2") (pintype "passive"))
      (node (ref "SENSOR2") (pin "2") (pinfunction "CSB_2") (pintype "input"))
      (node (ref "SENSOR2") (pin "6") (pinfunction "VDDIO_6") (pintype "power_in"))
      (node (ref "SENSOR2") (pin "8") (pinfunction "VDD_8") (pintype "power_in"))
      (node (ref "U2") (pin "17") (pinfunction "IO19_17") (pintype "bidirectional"))
    )
    (net (code "16") (name "INT_RTC") (class "Default")
      (node (ref "R1_PINH1") (pin "1") (pinfunction "1_1") (pintype "passive"))
      (node (ref "TP17") (pin "TP") (pinfunction "TP_TP") (pintype "input"))
      (node (ref "U2") (pin "8") (pinfunction "IO0_8") (pintype "bidirectional"))
      (node (ref "U3") (pin "3") (pinfunction "SQW/~{INT}_3") (pintype "output"))
    )
    (net (code "17") (name "IO{slash}BOOT") (class "Default")
      (node (ref "BOOT_BUTTON") (pin "3") (pinfunction "3_3") (pintype "passive"))
      (node (ref "BOOT_BUTTON") (pin "4") (pinfunction "4_4") (pintype "passive"))
      (node (ref "C6") (pin "1") (pinfunction "1_1") (pintype "passive"))
      (node (ref "R_BOOT") (pin "1") (pinfunction "1_1") (pintype "passive"))
      (node (ref "U2") (pin "15") (pinfunction "IO9_15") (pintype "bidirectional"))
    )
    (net (code "18") (name "IO{slash}CHANGE") (class "Default")
      (node (ref "C10") (pin "1") (pinfunction "1_1") (pintype "passive"))
      (node (ref "CHANGE_BUTTON") (pin "3") (pinfunction "3_3") (pintype "passive"))
      (node (ref "CHANGE_BUTTON") (pin "4") (pinfunction "4_4") (pintype "passive"))
      (node (ref "R_CHANGE") (pin "1") (pinfunction "1_1") (pintype "passive"))
      (node (ref "U2") (pin "23") (pinfunction "IO15_23") (pintype "bidirectional"))
    )
    (net (code "19") (name "MISO") (class "Default")
      (node (ref "D12") (pin "2") (pinfunction "2_2") (pintype "passive"))
      (node (ref "J2") (pin "P7") (pinfunction "DAT0_P7") (pintype "bidirectional"))
      (node (ref "R8") (pin "1") (pinfunction "1_1") (pintype "passive"))
      (node (ref "TP11") (pin "TP") (pinfunction "TP_TP") (pintype "input"))
      (node (ref "U1") (pin "2") (pinfunction "DO(IO1)_2") (pintype "bidirectional"))
      (node (ref "U2") (pin "27") (pinfunction "IO2_27") (pintype "bidirectional"))
    )
    (net (code "20") (name "MOSI") (class "Default")
      (node (ref "D11") (pin "2") (pinfunction "2_2") (pintype "passive"))
      (node (ref "J2") (pin "P3") (pinfunction "CMD_P3") (pintype "bidirectional"))
      (node (ref "J3") (pin "14") (pinfunction "14_14") (pintype "bidirectional"))
      (node (ref "R7") (pin "1") (pinfunction "1_1") (pintype "passive"))
      (node (ref "TP12") (pin "TP") (pinfunction "TP_TP") (pintype "input"))
      (node (ref "U1") (pin "5") (pinfunction "DI(IO0)_5") (pintype "bidirectional"))
      (node (ref "U2") (pin "7") (pinfunction "IO7_7") (pintype "bidirectional"))
    )
    (net (code "21") (name "Net-(CHG_LED-PadC)") (class "Default")
      (node (ref "CHG_LED") (pin "C") (pinfunction "C_C") (pintype "passive"))
      (node (ref "R1_BAT") (pin "1") (pinfunction "1_1") (pintype "passive"))
    )
    (net (code "22") (name "Net-(D2-CATHODE)") (class "Default")
      (node (ref "C1_BAT1") (pin "1") (pinfunction "1_1") (pintype "passive"))
      (node (ref "D2") (pin "1") (pinfunction "CATHODE_1") (pintype "bidirectional"))
      (node (ref "IC4") (pin "1") (pinfunction "VIN_1") (pintype "bidirectional"))
      (node (ref "IC4") (pin "3") (pinfunction "CE_3") (pintype "bidirectional"))
      (node (ref "Q1") (pin "2") (pinfunction "S_2") (pintype "bidirectional"))
    )
    (net (code "23") (name "Net-(D3-A)") (class "Default")
      (node (ref "C4") (pin "1") (pinfunction "1_1") (pintype "passive"))
      (node (ref "D3") (pin "2") (pinfunction "A_2") (pintype "bidirectional"))
      (node (ref "D4") (pin "1") (pinfunction "K_1") (pintype "bidirectional"))
    )
    (net (code "24") (name "Net-(D7-CATHODE)") (class "Default")
      (node (ref "D7") (pin "1") (pinfunction "CATHODE_1") (pintype "bidirectional"))
      (node (ref "R_CAPACITOR") (pin "1") (pinfunction "1_1") (pintype "passive"))
    )
    (net (code "25") (name "Net-(EPD_C1-Pad2)") (class "Default")
      (node (ref "EPD_C1") (pin "2") (pinfunction "2_2") (pintype "passive"))
      (node (ref "J3") (pin "4") (pinfunction "4_4") (pintype "bidirectional"))
    )
    (net (code "26") (name "Net-(EPD_C2-Pad2)") (class "Default")
      (node (ref "EPD_C2") (pin "2") (pinfunction "2_2") (pintype "passive"))
      (node (ref "J3") (pin "5") (pinfunction "5_5") (pintype "bidirectional"))
    )
    (net (code "27") (name "Net-(EPD_C6-Pad2)") (class "Default")
      (node (ref "EPD_C6") (pin "2") (pinfunction "2_2") (pintype "passive"))
      (node (ref "J3") (pin "18") (pinfunction "18_18") (pintype "bidirectional"))
    )
    (net (code "28") (name "Net-(EPD_C7-Pad2)") (class "Default")
      (node (ref "EPD_C7") (pin "2") (pinfunction "2_2") (pintype "passive"))
      (node (ref "J3") (pin "19") (pinfunction "19_19") (pintype "bidirectional"))
    )
    (net (code "29") (name "Net-(EPD_C8-Pad2)") (class "Default")
      (node (ref "EPD_C8") (pin "2") (pinfunction "2_2") (pintype "passive"))
      (node (ref "J3") (pin "20") (pinfunction "20_20") (pintype "bidirectional"))
    )
    (net (code "30") (name "Net-(EPD_C10-Pad2)") (class "Default")
      (node (ref "EPD_C10") (pin "2") (pinfunction "2_2") (pintype "passive"))
      (node (ref "J3") (pin "22") (pinfunction "22_22") (pintype "bidirectional"))
    )
    (net (code "31") (name "Net-(EPD_C12-Pad2)") (class "Default")
      (node (ref "EPD_C12") (pin "2") (pinfunction "2_2") (pintype "passive"))
      (node (ref "J3") (pin "24") (pinfunction "24_24") (pintype "bidirectional"))
    )
    (net (code "32") (name "Net-(IC1-CT)") (class "Default")
      (node (ref "C_DELAY") (pin "1") (pinfunction "1_1") (pintype "passive"))
      (node (ref "IC1") (pin "5") (pinfunction "CT_5") (pintype "bidirectional"))
    )
    (net (code "33") (name "Net-(J1-PadA5)") (class "Default")
      (node (ref "J1") (pin "A5") (pinfunction "A5_A5") (pintype "bidirectional"))
      (node (ref "R2-USB1") (pin "2") (pinfunction "2_2") (pintype "passive"))
    )
    (net (code "34") (name "Net-(J1-PadB5)") (class "Default")
      (node (ref "J1") (pin "B5") (pinfunction "B5_B5") (pintype "bidirectional"))
      (node (ref "R2-USB") (pin "1") (pinfunction "1_1") (pintype "passive"))
    )
    (net (code "35") (name "Net-(MCP73831-PROG)") (class "Default")
      (node (ref "MCP73831") (pin "5") (pinfunction "PROG_5") (pintype "input"))
      (node (ref "R2_BAT") (pin "2") (pinfunction "2_2") (pintype "passive"))
    )
    (net (code "36") (name "Net-(MCP73831-STAT)") (class "Default")
      (node (ref "MCP73831") (pin "1") (pinfunction "STAT_1") (pintype "output"))
      (node (ref "R1_BAT") (pin "2") (pinfunction "2_2") (pintype "passive"))
    )
    (net (code "37") (name "PREVGH") (class "Default")
      (node (ref "D5") (pin "1") (pinfunction "K_1") (pintype "bidirectional"))
      (node (ref "EPD_C9") (pin "2") (pinfunction "2_2") (pintype "passive"))
      (node (ref "J3") (pin "21") (pinfunction "21_21") (pintype "bidirectional"))
    )
    (net (code "38") (name "PREVGL") (class "Default")
      (node (ref "D4") (pin "2") (pinfunction "A_2") (pintype "bidirectional"))
      (node (ref "EPD_C11") (pin "2") (pinfunction "2_2") (pintype "passive"))
      (node (ref "J3") (pin "23") (pinfunction "23_23") (pintype "bidirectional"))
    )
    (net (code "39") (name "RESE") (class "Default")
      (node (ref "J3") (pin "3") (pinfunction "3_3") (pintype "bidirectional"))
      (node (ref "Q3") (pin "2") (pinfunction "S_2") (pintype "bidirectional"))
      (node (ref "R2") (pin "2") (pinfunction "2_2") (pintype "passive"))
      (node (ref "R3") (pin "1") (pinfunction "1_1") (pintype "passive"))
      (node (ref "R3") (pin "2") (pinfunction "2_2") (pintype "passive"))
      (node (ref "SJ1") (pin "2") (pinfunction "2_2") (pintype "passive"))
    )
    (net (code "40") (name "RESET") (class "Default")
      (node (ref "C5") (pin "1") (pinfunction "1_1") (pintype "passive"))
      (node (ref "IC1") (pin "1") (pinfunction "VOUT_1") (pintype "bidirectional"))
      (node (ref "RESET_BUTTON") (pin "3") (pinfunction "3_3") (pintype "passive"))
      (node (ref "RESET_BUTTON") (pin "4") (pinfunction "4_4") (pintype "passive"))
      (node (ref "R_RESET") (pin "1") (pinfunction "1_1") (pintype "passive"))
      (node (ref "U2") (pin "3") (pinfunction "EN_3") (pintype "input"))
    )
    (net (code "41") (name "RTC_RST") (class "Default")
      (node (ref "U2") (pin "16") (pinfunction "IO18_16") (pintype "bidirectional"))
      (node (ref "U3") (pin "4") (pinfunction "~{RST}_4") (pintype "input"))
    )
    (net (code "42") (name "RX") (class "Default")
      (node (ref "TP2") (pin "TP") (pinfunction "TP_TP") (pintype "input"))
      (node (ref "U2") (pin "24") (pinfunction "RXD0/GPIO17_24") (pintype "bidirectional"))
    )
    (net (code "43") (name "SCK") (class "Default")
      (node (ref "D10") (pin "2") (pinfunction "2_2") (pintype "passive"))
      (node (ref "J2") (pin "P5") (pinfunction "CLK_P5") (pintype "bidirectional"))
      (node (ref "J3") (pin "13") (pinfunction "13_13") (pintype "bidirectional"))
      (node (ref "R6") (pin "1") (pinfunction "1_1") (pintype "passive"))
      (node (ref "TP10") (pin "TP") (pinfunction "TP_TP") (pintype "input"))
      (node (ref "U1") (pin "6") (pinfunction "CLK_6") (pintype "input"))
      (node (ref "U2") (pin "6") (pinfunction "IO6_6") (pintype "bidirectional"))
    )
    (net (code "44") (name "SCL") (class "Default")
      (node (ref "J4") (pin "4") (pinfunction "4_4") (pintype "passive"))
      (node (ref "R2-PINH") (pin "1") (pinfunction "1_1") (pintype "passive"))
      (node (ref "SENSOR2") (pin "4") (pinfunction "SCK_4") (pintype "input"))
      (node (ref "U2") (pin "20") (pinfunction "IO22_20") (pintype "bidirectional"))
      (node (ref "U3") (pin "16") (pinfunction "SCL_16") (pintype "input"))
      (node (ref "U4") (pin "7") (pinfunction "SCL_7") (pintype "input"))
    )
    (net (code "45") (name "SDA") (class "Default")
      (node (ref "J4") (pin "3") (pinfunction "3_3") (pintype "passive"))
      (node (ref "R1_PINH") (pin "1") (pinfunction "1_1") (pintype "passive"))
      (node (ref "SENSOR2") (pin "3") (pinfunction "SDI_3") (pintype "bidirectional"))
      (node (ref "U2") (pin "19") (pinfunction "IO21_19") (pintype "bidirectional"))
      (node (ref "U3") (pin "15") (pinfunction "SDA_15") (pintype "bidirectional"))
      (node (ref "U4") (pin "8") (pinfunction "SDA_8") (pintype "bidirectional"))
    )
    (net (code "46") (name "SRC") (class "Default")
      (node (ref "C4") (pin "2") (pinfunction "2_2") (pintype "passive"))
      (node (ref "D5") (pin "2") (pinfunction "A_2") (pintype "bidirectional"))
      (node (ref "L1") (pin "1") (pinfunction "1_1") (pintype "passive"))
      (node (ref "Q3") (pin "3") (pinfunction "D_3") (pintype "bidirectional"))
    )
    (net (code "47") (name "SS_SD") (class "Default")
      (node (ref "D8") (pin "2") (pinfunction "2_2") (pintype "passive"))
      (node (ref "J2") (pin "P2") (pinfunction "CD/DAT3_P2") (pintype "bidirectional"))
      (node (ref "R10") (pin "1") (pinfunction "1_1") (pintype "passive"))
      (node (ref "U2") (pin "4") (pinfunction "IO4_4") (pintype "bidirectional"))
    )
    (net (code "48") (name "TX") (class "Default")
      (node (ref "TP1") (pin "TP") (pinfunction "TP_TP") (pintype "input"))
      (node (ref "U2") (pin "25") (pinfunction "TXD0/GPIO16_25") (pintype "bidirectional"))
    )
    (net (code "49") (name "USB_D+") (class "Default")
      (node (ref "D1") (pin "3") (pinfunction "I/O2_1_3") (pintype "bidirectional"))
      (node (ref "U2") (pin "14") (pinfunction "IO13_14") (pintype "bidirectional"))
    )
    (net (code "50") (name "USB_D-") (class "Default")
      (node (ref "D1") (pin "1") (pinfunction "I/O1_1_1") (pintype "bidirectional"))
      (node (ref "U2") (pin "13") (pinfunction "IO12_13") (pintype "bidirectional"))
    )
    (net (code "51") (name "VBAT") (class "Default")
      (node (ref "C2_BAT") (pin "1") (pinfunction "1_1") (pintype "passive"))
      (node (ref "MCP73831") (pin "3") (pinfunction "VBAT_3") (pintype "power_in"))
      (node (ref "Q1") (pin "3") (pinfunction "D_3") (pintype "bidirectional"))
      (node (ref "TP3") (pin "TP") (pinfunction "TP_TP") (pintype "input"))
      (node (ref "U4") (pin "2") (pinfunction "CELL_2") (pintype "power_in"))
      (node (ref "U4") (pin "3") (pinfunction "VDD_3") (pintype "power_in"))
    )
    (net (code "52") (name "VBUS") (class "Default")
      (node (ref "C1_BAT") (pin "1") (pinfunction "1_1") (pintype "passive"))
      (node (ref "C4_USB") (pin "1") (pinfunction "1_1") (pintype "passive"))
      (node (ref "C5_USB") (pin "1") (pinfunction "1_1") (pintype "passive"))
      (node (ref "CHG_LED") (pin "A") (pinfunction "A_A") (pintype "passive"))
      (node (ref "D1") (pin "5") (pinfunction "VBUS_5") (pintype "bidirectional"))
      (node (ref "D2") (pin "2") (pinfunction "ANODE_2") (pintype "bidirectional"))
      (node (ref "MCP73831") (pin "4") (pinfunction "VIN_4") (pintype "power_in"))
      (node (ref "PFMF.050.1") (pin "2") (pinfunction "2_2") (pintype "passive"))
      (node (ref "Q1") (pin "1") (pinfunction "G_1") (pintype "bidirectional"))
      (node (ref "R1_PWRUSB") (pin "2") (pinfunction "2_2") (pintype "passive"))
      (node (ref "TP16") (pin "TP") (pinfunction "TP_TP") (pintype "input"))
    )
    (net (code "53") (name "VRTC") (class "Default")
      (node (ref "C10_SUPERCAP") (pin "1") (pinfunction "1_1") (pintype "passive"))
      (node (ref "C8") (pin "1") (pinfunction "1_1") (pintype "passive"))
      (node (ref "R_CAPACITOR") (pin "2") (pinfunction "2_2") (pintype "passive"))
      (node (ref "U3") (pin "14") (pinfunction "VBAT_14") (pintype "power_in"))
    )
    (net (code "54") (name "VUSB") (class "Default")
      (node (ref "J1") (pin "A4") (pinfunction "A4_A4") (pintype "bidirectional"))
      (node (ref "J1") (pin "A9") (pinfunction "A9_A9") (pintype "bidirectional"))
      (node (ref "J1") (pin "B4") (pinfunction "B4_B4") (pintype "bidirectional"))
      (node (ref "J1") (pin "B9") (pinfunction "B9_B9") (pintype "bidirectional"))
      (node (ref "PFMF.050.1") (pin "1") (pinfunction "1_1") (pintype "passive"))
    )
    (net (code "55") (name "unconnected-(IC1-NC-Pad4)") (class "Default")
      (node (ref "IC1") (pin "4") (pinfunction "NC_4") (pintype "no_connect"))
    )
    (net (code "56") (name "unconnected-(IC4-NC-Pad4)") (class "Default")
      (node (ref "IC4") (pin "4") (pinfunction "NC_4") (pintype "no_connect"))
    )
    (net (code "57") (name "unconnected-(J1-PadA8)") (class "Default")
      (node (ref "J1") (pin "A8") (pinfunction "A8_A8") (pintype "bidirectional"))
    )
    (net (code "58") (name "unconnected-(J1-PadB8)") (class "Default")
      (node (ref "J1") (pin "B8") (pinfunction "B8_B8") (pintype "bidirectional"))
    )
    (net (code "59") (name "unconnected-(J2-DAT1-PadP8)") (class "Default")
      (node (ref "J2") (pin "P8") (pinfunction "DAT1_P8") (pintype "bidirectional"))
    )
    (net (code "60") (name "unconnected-(J2-DAT2-PadP1)") (class "Default")
      (node (ref "J2") (pin "P1") (pinfunction "DAT2_P1") (pintype "bidirectional"))
    )
    (net (code "61") (name "unconnected-(J2-DETECTION_1-PadS1)") (class "Default")
      (node (ref "J2") (pin "S1") (pinfunction "DETECTION_1_S1") (pintype "bidirectional"))
    )
    (net (code "62") (name "unconnected-(J2-DETECTION_2-PadS2)") (class "Default")
      (node (ref "J2") (pin "S2") (pinfunction "DETECTION_2_S2") (pintype "bidirectional"))
    )
    (net (code "63") (name "unconnected-(J3-Pad1)") (class "Default")
      (node (ref "J3") (pin "1") (pinfunction "1_1") (pintype "bidirectional"))
    )
    (net (code "64") (name "unconnected-(J3-Pad6)") (class "Default")
      (node (ref "J3") (pin "6") (pinfunction "6_6") (pintype "bidirectional"))
    )
    (net (code "65") (name "unconnected-(J3-Pad7)") (class "Default")
      (node (ref "J3") (pin "7") (pinfunction "7_7") (pintype "bidirectional"))
    )
    (net (code "66") (name "unconnected-(U2-NC-Pad22)") (class "Default")
      (node (ref "U2") (pin "22") (pinfunction "NC_22") (pintype "no_connect"))
    )
    (net (code "67") (name "unconnected-(U4-~{ALERT}-Pad5)") (class "Default")
      (node (ref "U4") (pin "5") (pinfunction "~{ALERT}_5") (pintype "output"))
    )
  )
)
